# switch-20mm-mk-1_0.net
KiCad netlist of a schematic drawn in EAGLE
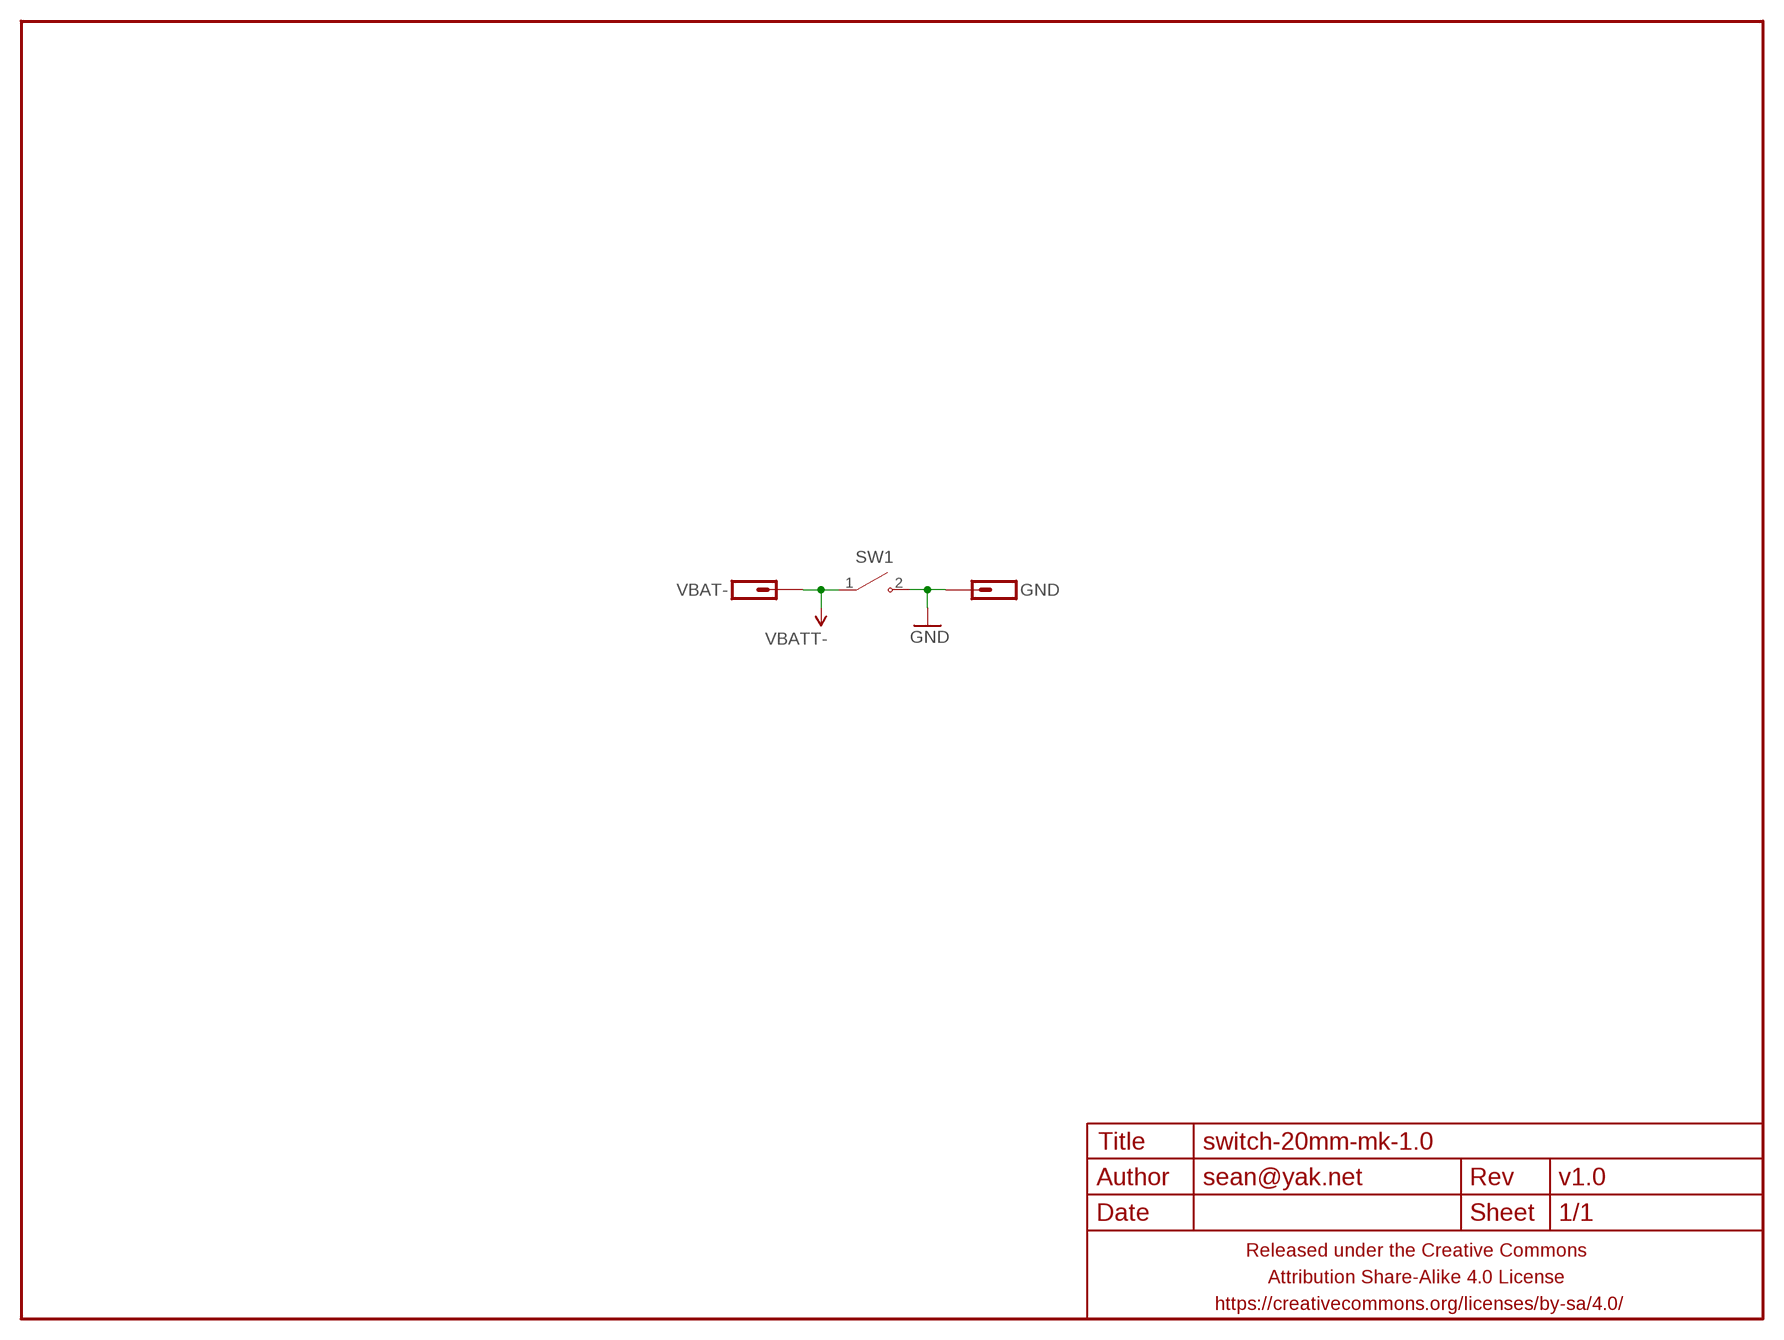
[diagram p0: schematic, sheet 1]

(export (version "E")
  (design (tool "Eeschema 10.0.6"))
  (components
    (comp (ref "FRAME1")
      (value "FRAME-LETTERNO_PACKAGE")
      (footprint "eagle-import:DUMMY")
      (fields (field (name "DESIGNER") "sean@yak.net") (field (name "VERSION") "v1.0"))
      (libsource (lib "eagle-import") (part "FRAME-LETTERNO_PACKAGE"))
    )
    (comp (ref "GND")
      (value "M01NOT-A-VIA-NOPE")
      (footprint "eagle-import:1X01_NOSILK_NOSTOP")
      (libsource (lib "eagle-import") (part "M01NOT-A-VIA-NOPE"))
    )
    (comp (ref "SW1")
      (value "SWITCH-SPSTOMTEN-1288-PTH")
      (footprint "eagle-import:OMTEN-1288-PTH")
      (libsource (lib "eagle-import") (part "SWITCH-SPSTOMTEN-1288-PTH"))
    )
    (comp (ref "VBAT-")
      (value "M01PTH-1MM-CIR-NS")
      (footprint "eagle-import:1X01-1MM-CIR-NS")
      (libsource (lib "eagle-import") (part "M01PTH-1MM-CIR-NS"))
    )
  )
  (nets
    (net (code "1") (name "GND") (class "Default")
      (node (ref "GND") (pin "P$1") (pinfunction "1_P$1") (pintype "passive"))
      (node (ref "SW1") (pin "2") (pinfunction "NO_2") (pintype "bidirectional"))
    )
    (net (code "2") (name "VBATT-") (class "Default")
      (node (ref "SW1") (pin "1") (pinfunction "COM_1") (pintype "bidirectional"))
      (node (ref "VBAT-") (pin "1") (pinfunction "1_1") (pintype "passive"))
    )
  )
)
